# SerialTrainSensor.net
KiCad netlist of a schematic drawn in EAGLE
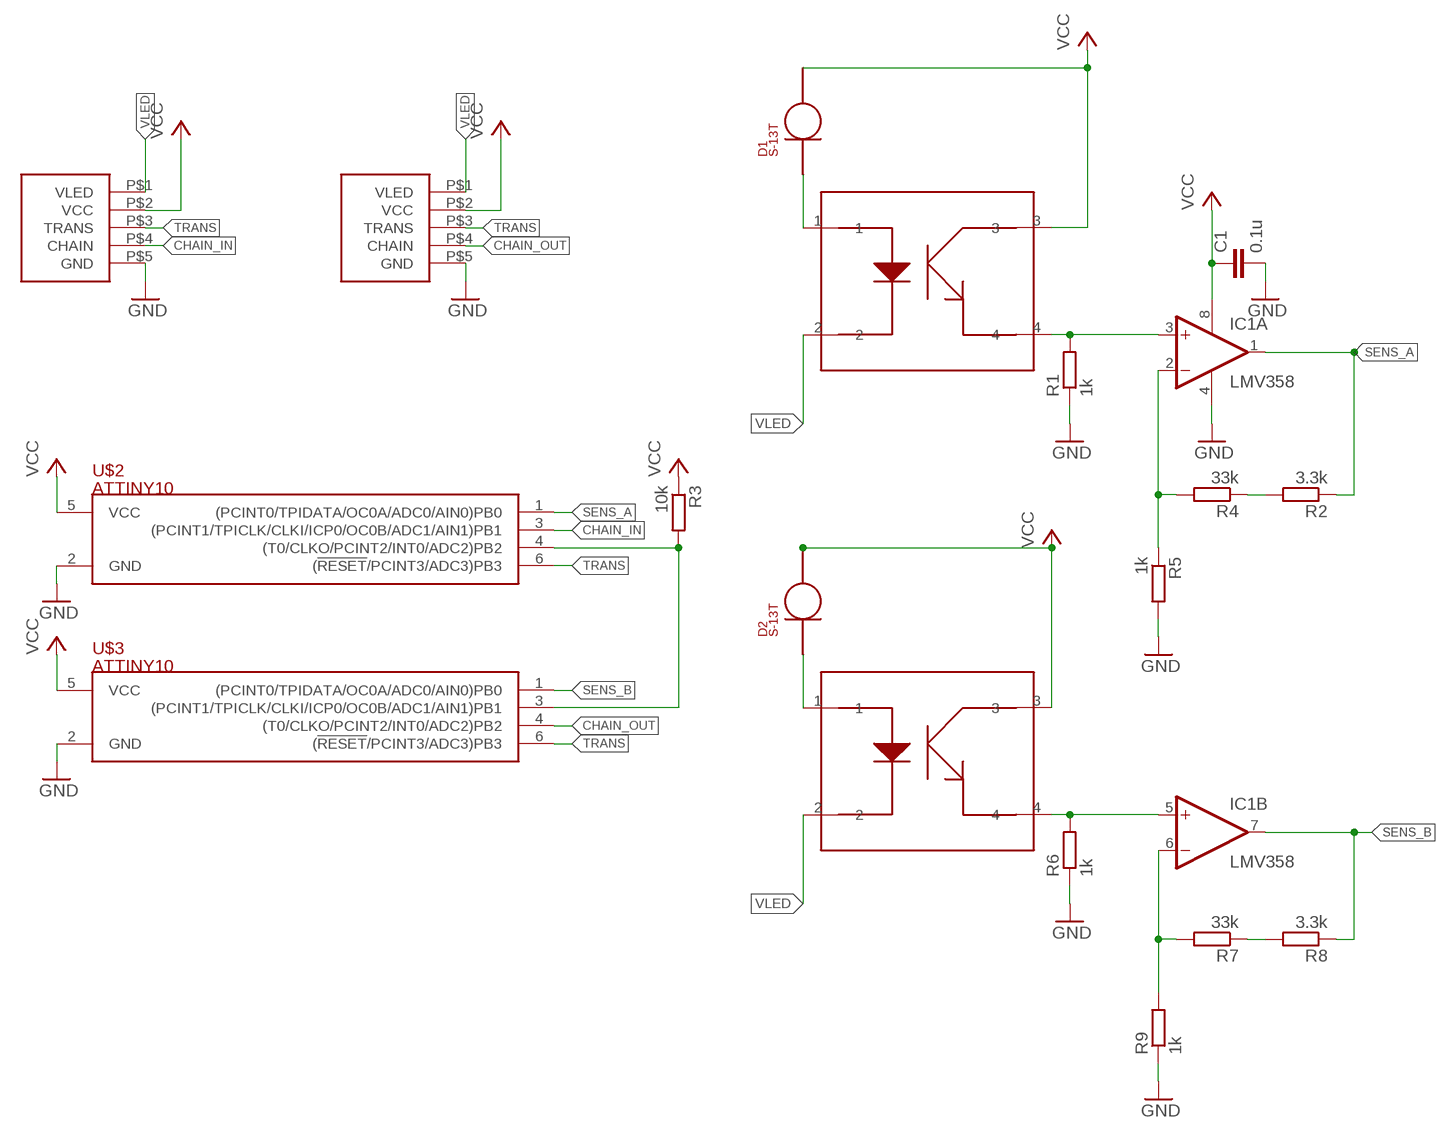
[diagram p0: schematic, sheet 1]

(export (version "E")
  (design (tool "Eeschema 10.0.6"))
  (components
    (comp (ref "C1")
      (value "0.1u")
      (footprint "eagle-import:C0603")
      (libsource (lib "eagle-import") (part "C-EUC0603"))
    )
    (comp (ref "D1")
      (value "S-13T")
      (footprint "eagle-import:S-1_3T")
      (libsource (lib "eagle-import") (part "S-13T"))
    )
    (comp (ref "D2")
      (value "S-13T")
      (footprint "eagle-import:S-1_3T")
      (libsource (lib "eagle-import") (part "S-13T"))
    )
    (comp (ref "IC1")
      (value "LMV358")
      (footprint "eagle-import:TSSOP8")
      (libsource (lib "eagle-import") (part "LMV358?"))
    )
    (comp (ref "R1")
      (value "1k")
      (footprint "eagle-import:R0603")
      (libsource (lib "eagle-import") (part "R-EU_R0603"))
    )
    (comp (ref "R2")
      (value "3.3k")
      (footprint "eagle-import:R0603")
      (libsource (lib "eagle-import") (part "R-EU_R0603"))
    )
    (comp (ref "R3")
      (value "10k")
      (footprint "eagle-import:R0603")
      (libsource (lib "eagle-import") (part "R-EU_R0603"))
    )
    (comp (ref "R4")
      (value "33k")
      (footprint "eagle-import:R0603")
      (libsource (lib "eagle-import") (part "R-EU_R0603"))
    )
    (comp (ref "R5")
      (value "1k")
      (footprint "eagle-import:R0603")
      (libsource (lib "eagle-import") (part "R-EU_R0603"))
    )
    (comp (ref "R6")
      (value "1k")
      (footprint "eagle-import:R0603")
      (libsource (lib "eagle-import") (part "R-EU_R0603"))
    )
    (comp (ref "R7")
      (value "33k")
      (footprint "eagle-import:R0603")
      (libsource (lib "eagle-import") (part "R-EU_R0603"))
    )
    (comp (ref "R8")
      (value "3.3k")
      (footprint "eagle-import:R0603")
      (libsource (lib "eagle-import") (part "R-EU_R0603"))
    )
    (comp (ref "R9")
      (value "1k")
      (footprint "eagle-import:R0603")
      (libsource (lib "eagle-import") (part "R-EU_R0603"))
    )
    (comp (ref "SMD1")
      (value "SERIAL_SENSORHALF")
      (footprint "eagle-import:SERIAL_5_HALF")
      (libsource (lib "eagle-import") (part "SERIAL_SENSORHALF"))
    )
    (comp (ref "SMD2")
      (value "SERIAL_SENSORHALF")
      (footprint "eagle-import:SERIAL_5_HALF")
      (libsource (lib "eagle-import") (part "SERIAL_SENSORHALF"))
    )
    (comp (ref "U$1")
      (value "TPR-105F")
      (footprint "eagle-import:TPR-105F")
      (libsource (lib "eagle-import") (part "TPR-105F"))
    )
    (comp (ref "U$2")
      (value "ATTINY10")
      (footprint "eagle-import:SOT-23")
      (libsource (lib "eagle-import") (part "ATTINY10"))
    )
    (comp (ref "U$3")
      (value "ATTINY10")
      (footprint "eagle-import:SOT-23")
      (libsource (lib "eagle-import") (part "ATTINY10"))
    )
    (comp (ref "U$4")
      (value "TPR-105F")
      (footprint "eagle-import:TPR-105F")
      (libsource (lib "eagle-import") (part "TPR-105F"))
    )
  )
  (nets
    (net (code "1") (name "CHAIN_IN") (class "Default")
      (node (ref "SMD1") (pin "P$4") (pinfunction "CHAIN_P$4") (pintype "bidirectional"))
      (node (ref "U$2") (pin "3") (pinfunction "(PCINT1/TPICLK/CLKI/ICP0/OC0B/ADC1/AIN1)PB1_3") (pintype "bidirectional"))
    )
    (net (code "2") (name "CHAIN_OUT") (class "Default")
      (node (ref "SMD2") (pin "P$4") (pinfunction "CHAIN_P$4") (pintype "bidirectional"))
      (node (ref "U$3") (pin "4") (pinfunction "(T0/CLKO/PCINT2/INT0/ADC2)PB2_4") (pintype "bidirectional"))
    )
    (net (code "3") (name "GND") (class "Default")
      (node (ref "C1") (pin "2") (pinfunction "2_2") (pintype "passive"))
      (node (ref "IC1") (pin "4") (pinfunction "V-_4") (pintype "power_in"))
      (node (ref "R1") (pin "1") (pinfunction "1_1") (pintype "passive"))
      (node (ref "R5") (pin "2") (pinfunction "2_2") (pintype "passive"))
      (node (ref "R6") (pin "1") (pinfunction "1_1") (pintype "passive"))
      (node (ref "R9") (pin "1") (pinfunction "1_1") (pintype "passive"))
      (node (ref "SMD1") (pin "P$5") (pinfunction "GND_P$5") (pintype "bidirectional"))
      (node (ref "SMD2") (pin "P$5") (pinfunction "GND_P$5") (pintype "bidirectional"))
      (node (ref "U$2") (pin "2") (pinfunction "GND_2") (pintype "power_in"))
      (node (ref "U$3") (pin "2") (pinfunction "GND_2") (pintype "power_in"))
    )
    (net (code "4") (name "Net-(D1-PadC)") (class "Default")
      (node (ref "D1") (pin "C") (pinfunction "C_C") (pintype "bidirectional"))
      (node (ref "U$1") (pin "1") (pinfunction "1_1") (pintype "bidirectional"))
    )
    (net (code "5") (name "Net-(D2-PadC)") (class "Default")
      (node (ref "D2") (pin "C") (pinfunction "C_C") (pintype "bidirectional"))
      (node (ref "U$4") (pin "1") (pinfunction "1_1") (pintype "bidirectional"))
    )
    (net (code "6") (name "Net-(IC1A-+IN)") (class "Default")
      (node (ref "IC1") (pin "3") (pinfunction "+IN_3") (pintype "input"))
      (node (ref "R1") (pin "2") (pinfunction "2_2") (pintype "passive"))
      (node (ref "U$1") (pin "4") (pinfunction "4_4") (pintype "bidirectional"))
    )
    (net (code "7") (name "Net-(IC1A--IN)") (class "Default")
      (node (ref "IC1") (pin "2") (pinfunction "-IN_2") (pintype "input"))
      (node (ref "R4") (pin "2") (pinfunction "2_2") (pintype "passive"))
      (node (ref "R5") (pin "1") (pinfunction "1_1") (pintype "passive"))
    )
    (net (code "8") (name "Net-(IC1B-+IN)") (class "Default")
      (node (ref "IC1") (pin "5") (pinfunction "+IN_5") (pintype "input"))
      (node (ref "R6") (pin "2") (pinfunction "2_2") (pintype "passive"))
      (node (ref "U$4") (pin "4") (pinfunction "4_4") (pintype "bidirectional"))
    )
    (net (code "9") (name "Net-(IC1B--IN)") (class "Default")
      (node (ref "IC1") (pin "6") (pinfunction "-IN_6") (pintype "input"))
      (node (ref "R7") (pin "2") (pinfunction "2_2") (pintype "passive"))
      (node (ref "R9") (pin "2") (pinfunction "2_2") (pintype "passive"))
    )
    (net (code "10") (name "Net-(R2-Pad2)") (class "Default")
      (node (ref "R2") (pin "2") (pinfunction "2_2") (pintype "passive"))
      (node (ref "R4") (pin "1") (pinfunction "1_1") (pintype "passive"))
    )
    (net (code "11") (name "Net-(R7-Pad1)") (class "Default")
      (node (ref "R7") (pin "1") (pinfunction "1_1") (pintype "passive"))
      (node (ref "R8") (pin "2") (pinfunction "2_2") (pintype "passive"))
    )
    (net (code "12") (name "Net-(U$2-(T0{slash}CLKO{slash}PCINT2{slash}INT0{slash}ADC2)PB2)") (class "Default")
      (node (ref "R3") (pin "2") (pinfunction "2_2") (pintype "passive"))
      (node (ref "U$2") (pin "4") (pinfunction "(T0/CLKO/PCINT2/INT0/ADC2)PB2_4") (pintype "bidirectional"))
      (node (ref "U$3") (pin "3") (pinfunction "(PCINT1/TPICLK/CLKI/ICP0/OC0B/ADC1/AIN1)PB1_3") (pintype "bidirectional"))
    )
    (net (code "13") (name "SENS_A") (class "Default")
      (node (ref "IC1") (pin "1") (pinfunction "OUT_1") (pintype "output"))
      (node (ref "R2") (pin "1") (pinfunction "1_1") (pintype "passive"))
      (node (ref "U$2") (pin "1") (pinfunction "(PCINT0/TPIDATA/OC0A/ADC0/AIN0)PB0_1") (pintype "bidirectional"))
    )
    (net (code "14") (name "SENS_B") (class "Default")
      (node (ref "IC1") (pin "7") (pinfunction "OUT_7") (pintype "output"))
      (node (ref "R8") (pin "1") (pinfunction "1_1") (pintype "passive"))
      (node (ref "U$3") (pin "1") (pinfunction "(PCINT0/TPIDATA/OC0A/ADC0/AIN0)PB0_1") (pintype "bidirectional"))
    )
    (net (code "15") (name "TRANS") (class "Default")
      (node (ref "SMD1") (pin "P$3") (pinfunction "TRANS_P$3") (pintype "bidirectional"))
      (node (ref "SMD2") (pin "P$3") (pinfunction "TRANS_P$3") (pintype "bidirectional"))
      (node (ref "U$2") (pin "6") (pinfunction "(~{RESET}/PCINT3/ADC3)PB3_6") (pintype "bidirectional"))
      (node (ref "U$3") (pin "6") (pinfunction "(~{RESET}/PCINT3/ADC3)PB3_6") (pintype "bidirectional"))
    )
    (net (code "16") (name "VCC") (class "Default")
      (node (ref "C1") (pin "1") (pinfunction "1_1") (pintype "passive"))
      (node (ref "D1") (pin "A") (pinfunction "A_A") (pintype "bidirectional"))
      (node (ref "D2") (pin "A") (pinfunction "A_A") (pintype "bidirectional"))
      (node (ref "IC1") (pin "8") (pinfunction "V+_8") (pintype "power_in"))
      (node (ref "R3") (pin "1") (pinfunction "1_1") (pintype "passive"))
      (node (ref "SMD1") (pin "P$2") (pinfunction "VCC_P$2") (pintype "bidirectional"))
      (node (ref "SMD2") (pin "P$2") (pinfunction "VCC_P$2") (pintype "bidirectional"))
      (node (ref "U$1") (pin "3") (pinfunction "3_3") (pintype "bidirectional"))
      (node (ref "U$2") (pin "5") (pinfunction "VCC_5") (pintype "power_in"))
      (node (ref "U$3") (pin "5") (pinfunction "VCC_5") (pintype "power_in"))
      (node (ref "U$4") (pin "3") (pinfunction "3_3") (pintype "bidirectional"))
    )
    (net (code "17") (name "VLED") (class "Default")
      (node (ref "SMD1") (pin "P$1") (pinfunction "VLED_P$1") (pintype "bidirectional"))
      (node (ref "SMD2") (pin "P$1") (pinfunction "VLED_P$1") (pintype "bidirectional"))
      (node (ref "U$1") (pin "2") (pinfunction "2_2") (pintype "bidirectional"))
      (node (ref "U$4") (pin "2") (pinfunction "2_2") (pintype "bidirectional"))
    )
  )
)
